# espyollucopy.net
KiCad netlist of a schematic drawn in EAGLE
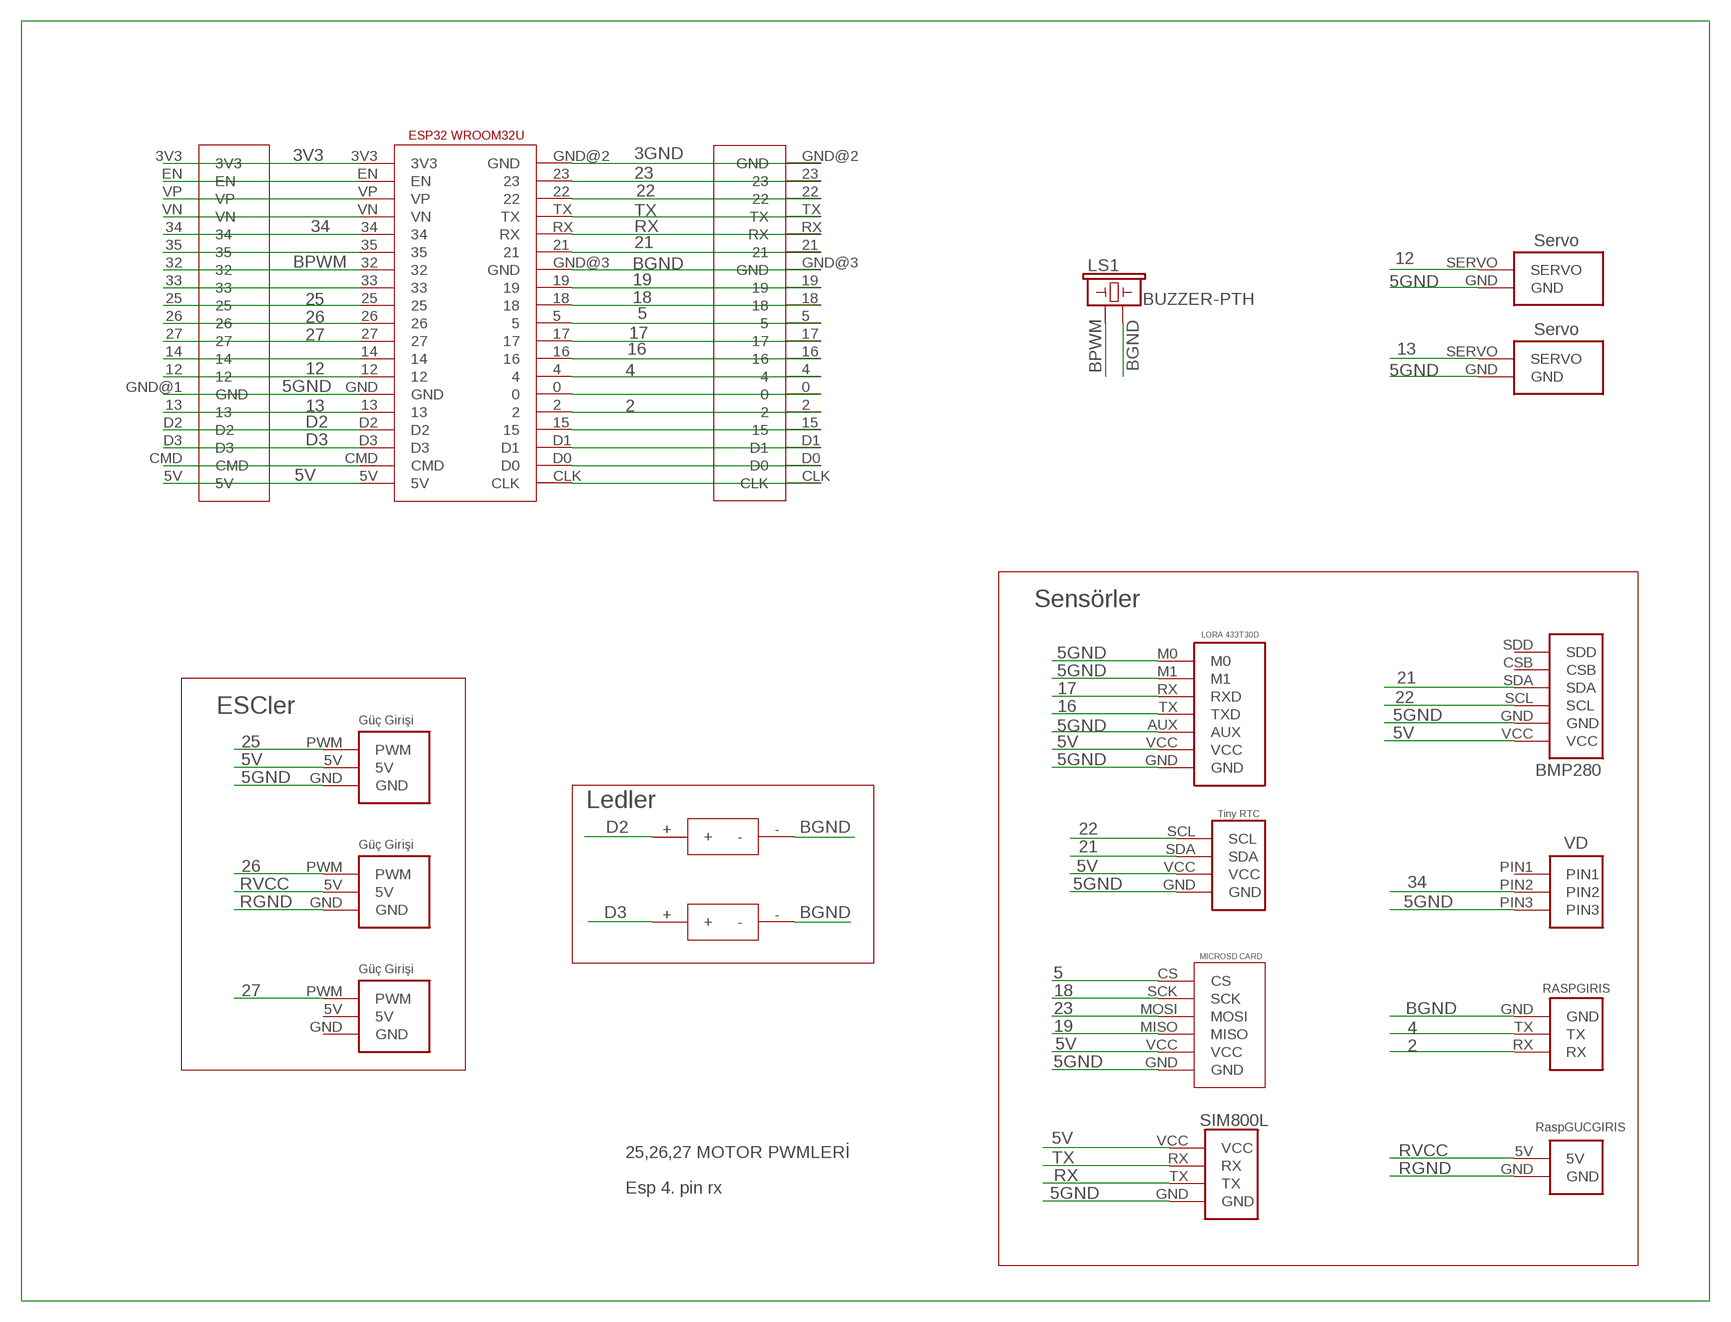
[diagram p0: schematic, sheet 1]

(export (version "E")
  (design (tool "Eeschema 10.0.6"))
  (components
    (comp (ref "BMP1")
      (value "BMP280")
      (footprint "eagle-import:BMP280")
      (libsource (lib "eagle-import") (part "BMP280"))
    )
    (comp (ref "LS1")
      (value "BUZZER-PTH")
      (footprint "eagle-import:BUZZER-12MM")
      (libsource (lib "eagle-import") (part "BUZZER-PTH"))
    )
    (comp (ref "U$1")
      (value "TINYRTC")
      (footprint "eagle-import:TINYRTC")
      (libsource (lib "eagle-import") (part "TINYRTC"))
    )
    (comp (ref "U$2")
      (value "VOLTAGE_DIVIDER")
      (footprint "eagle-import:VOLTAGE_DIVIDER")
      (libsource (lib "eagle-import") (part "VOLTAGE_DIVIDER"))
    )
    (comp (ref "U$3")
      (value "RASPGIRIS")
      (footprint "eagle-import:RASPGIRIS")
      (libsource (lib "eagle-import") (part "RASPGIRIS"))
    )
    (comp (ref "U$4")
      (value "ESP32WROOM32U")
      (footprint "eagle-import:ESP32WROOM32U")
      (libsource (lib "eagle-import") (part "ESP32WROOM32U"))
    )
    (comp (ref "U$5")
      (value "LORAFULLSIZE")
      (footprint "eagle-import:LORAFULLSIZE")
      (libsource (lib "eagle-import") (part "LORAFULLSIZE"))
    )
    (comp (ref "U$6")
      (value "MICROSD_CARD")
      (footprint "eagle-import:MICROSD_CARD")
      (libsource (lib "eagle-import") (part "MICROSD_CARD"))
    )
    (comp (ref "U$7")
      (value "SERVO_SIGNAL")
      (footprint "eagle-import:SERVO_SIGNAL")
      (libsource (lib "eagle-import") (part "SERVO_SIGNAL"))
    )
    (comp (ref "U$8")
      (value "SIM800L")
      (footprint "eagle-import:SIM800L")
      (libsource (lib "eagle-import") (part "SIM800L"))
    )
    (comp (ref "U$9")
      (value "SERVO_SIGNAL")
      (footprint "eagle-import:SERVO_SIGNAL")
      (libsource (lib "eagle-import") (part "SERVO_SIGNAL"))
    )
    (comp (ref "U$10")
      (value "RASPGUCGIRIS")
      (footprint "eagle-import:RASPGUCGIRIS")
      (libsource (lib "eagle-import") (part "RASPGUCGIRIS"))
    )
    (comp (ref "U$11")
      (value "ESC_GIRIS")
      (footprint "eagle-import:ESC_GIRIS")
      (libsource (lib "eagle-import") (part "ESC_GIRIS"))
    )
    (comp (ref "U$12")
      (value "ESC_GIRIS")
      (footprint "eagle-import:ESC_GIRIS")
      (libsource (lib "eagle-import") (part "ESC_GIRIS"))
    )
    (comp (ref "U$13")
      (value "ESC_GIRIS")
      (footprint "eagle-import:ESC_GIRIS")
      (libsource (lib "eagle-import") (part "ESC_GIRIS"))
    )
    (comp (ref "U$14")
      (value "ESPSAGPIN")
      (footprint "eagle-import:ESPSAGPIN")
      (libsource (lib "eagle-import") (part "ESPSAGPIN"))
    )
    (comp (ref "U$15")
      (value "ESPSOLPIN")
      (footprint "eagle-import:ESPSOLPIN")
      (libsource (lib "eagle-import") (part "ESPSOLPIN"))
    )
    (comp (ref "U$17")
      (value "LED")
      (footprint "eagle-import:LED")
      (libsource (lib "eagle-import") (part "LED"))
    )
    (comp (ref "U$18")
      (value "LED")
      (footprint "eagle-import:LED")
      (libsource (lib "eagle-import") (part "LED"))
    )
  )
  (nets
    (net (code "1") (name "/2") (class "Default")
      (node (ref "U$14") (pin "2") (pinfunction "2_2") (pintype "bidirectional"))
      (node (ref "U$3") (pin "RX") (pinfunction "RX_RX") (pintype "bidirectional"))
      (node (ref "U$4") (pin "2") (pinfunction "2_2") (pintype "bidirectional"))
    )
    (net (code "2") (name "/3GND") (class "Default")
      (node (ref "U$14") (pin "GND@2") (pinfunction "GND_GND@2") (pintype "bidirectional"))
      (node (ref "U$4") (pin "GND@2") (pinfunction "GND_GND@2") (pintype "bidirectional"))
    )
    (net (code "3") (name "/3V3") (class "Default")
      (node (ref "U$15") (pin "3V3") (pinfunction "3V3_3V3") (pintype "bidirectional"))
      (node (ref "U$4") (pin "3V3") (pinfunction "3V3_3V3") (pintype "bidirectional"))
    )
    (net (code "4") (name "/4") (class "Default")
      (node (ref "U$14") (pin "4") (pinfunction "4_4") (pintype "bidirectional"))
      (node (ref "U$3") (pin "TX") (pinfunction "TX_TX") (pintype "bidirectional"))
      (node (ref "U$4") (pin "4") (pinfunction "4_4") (pintype "bidirectional"))
    )
    (net (code "5") (name "/5") (class "Default")
      (node (ref "U$14") (pin "5") (pinfunction "5_5") (pintype "bidirectional"))
      (node (ref "U$4") (pin "5") (pinfunction "5_5") (pintype "bidirectional"))
      (node (ref "U$6") (pin "CS") (pinfunction "CS_CS") (pintype "bidirectional"))
    )
    (net (code "6") (name "/5GND") (class "Default")
      (node (ref "BMP1") (pin "GND") (pinfunction "GND_GND") (pintype "bidirectional"))
      (node (ref "U$1") (pin "GND") (pinfunction "GND_GND") (pintype "bidirectional"))
      (node (ref "U$11") (pin "GND") (pinfunction "GND_GND") (pintype "bidirectional"))
      (node (ref "U$15") (pin "GND@1") (pinfunction "GND_GND@1") (pintype "bidirectional"))
      (node (ref "U$2") (pin "PIN3") (pinfunction "PIN3_PIN3") (pintype "bidirectional"))
      (node (ref "U$4") (pin "GND") (pinfunction "GND_GND") (pintype "bidirectional"))
      (node (ref "U$5") (pin "AUX") (pinfunction "AUX_AUX") (pintype "bidirectional"))
      (node (ref "U$5") (pin "GND") (pinfunction "GND_GND") (pintype "bidirectional"))
      (node (ref "U$5") (pin "M0") (pinfunction "M0_M0") (pintype "bidirectional"))
      (node (ref "U$5") (pin "M1") (pinfunction "M1_M1") (pintype "bidirectional"))
      (node (ref "U$6") (pin "GND") (pinfunction "GND_GND") (pintype "bidirectional"))
      (node (ref "U$7") (pin "GND") (pinfunction "GND_GND") (pintype "bidirectional"))
      (node (ref "U$8") (pin "GND") (pinfunction "GND_GND") (pintype "bidirectional"))
      (node (ref "U$9") (pin "GND") (pinfunction "GND_GND") (pintype "bidirectional"))
    )
    (net (code "7") (name "/5V") (class "Default")
      (node (ref "BMP1") (pin "VCC") (pinfunction "VCC_VCC") (pintype "bidirectional"))
      (node (ref "U$1") (pin "VCC") (pinfunction "VCC_VCC") (pintype "bidirectional"))
      (node (ref "U$11") (pin "5V") (pinfunction "5V_5V") (pintype "bidirectional"))
      (node (ref "U$15") (pin "5V") (pinfunction "5V_5V") (pintype "bidirectional"))
      (node (ref "U$4") (pin "5V") (pinfunction "5V_5V") (pintype "bidirectional"))
      (node (ref "U$5") (pin "VCC") (pinfunction "VCC_VCC") (pintype "bidirectional"))
      (node (ref "U$6") (pin "VCC") (pinfunction "VCC_VCC") (pintype "bidirectional"))
      (node (ref "U$8") (pin "VCC") (pinfunction "VCC_VCC") (pintype "bidirectional"))
    )
    (net (code "8") (name "/12") (class "Default")
      (node (ref "U$15") (pin "12") (pinfunction "12_12") (pintype "bidirectional"))
      (node (ref "U$4") (pin "12") (pinfunction "12_12") (pintype "bidirectional"))
      (node (ref "U$7") (pin "SERVO") (pinfunction "SERVO_SERVO") (pintype "bidirectional"))
    )
    (net (code "9") (name "/13") (class "Default")
      (node (ref "U$15") (pin "13") (pinfunction "13_13") (pintype "bidirectional"))
      (node (ref "U$4") (pin "13") (pinfunction "13_13") (pintype "bidirectional"))
      (node (ref "U$9") (pin "SERVO") (pinfunction "SERVO_SERVO") (pintype "bidirectional"))
    )
    (net (code "10") (name "/16") (class "Default")
      (node (ref "U$14") (pin "16") (pinfunction "16_16") (pintype "bidirectional"))
      (node (ref "U$4") (pin "16") (pinfunction "16_16") (pintype "bidirectional"))
      (node (ref "U$5") (pin "TX") (pinfunction "TXD_TX") (pintype "bidirectional"))
    )
    (net (code "11") (name "/17") (class "Default")
      (node (ref "U$14") (pin "17") (pinfunction "17_17") (pintype "bidirectional"))
      (node (ref "U$4") (pin "17") (pinfunction "17_17") (pintype "bidirectional"))
      (node (ref "U$5") (pin "RX") (pinfunction "RXD_RX") (pintype "bidirectional"))
    )
    (net (code "12") (name "/18") (class "Default")
      (node (ref "U$14") (pin "18") (pinfunction "18_18") (pintype "bidirectional"))
      (node (ref "U$4") (pin "18") (pinfunction "18_18") (pintype "bidirectional"))
      (node (ref "U$6") (pin "SCK") (pinfunction "SCK_SCK") (pintype "bidirectional"))
    )
    (net (code "13") (name "/19") (class "Default")
      (node (ref "U$14") (pin "19") (pinfunction "19_19") (pintype "bidirectional"))
      (node (ref "U$4") (pin "19") (pinfunction "19_19") (pintype "bidirectional"))
      (node (ref "U$6") (pin "MISO") (pinfunction "MISO_MISO") (pintype "bidirectional"))
    )
    (net (code "14") (name "/21") (class "Default")
      (node (ref "BMP1") (pin "SDA") (pinfunction "SDA_SDA") (pintype "bidirectional"))
      (node (ref "U$1") (pin "SDA") (pinfunction "SDA_SDA") (pintype "bidirectional"))
      (node (ref "U$14") (pin "21") (pinfunction "21_21") (pintype "bidirectional"))
      (node (ref "U$4") (pin "21") (pinfunction "21_21") (pintype "bidirectional"))
    )
    (net (code "15") (name "/22") (class "Default")
      (node (ref "BMP1") (pin "SCL") (pinfunction "SCL_SCL") (pintype "bidirectional"))
      (node (ref "U$1") (pin "SCL") (pinfunction "SCL_SCL") (pintype "bidirectional"))
      (node (ref "U$14") (pin "22") (pinfunction "22_22") (pintype "bidirectional"))
      (node (ref "U$4") (pin "22") (pinfunction "22_22") (pintype "bidirectional"))
    )
    (net (code "16") (name "/23") (class "Default")
      (node (ref "U$14") (pin "23") (pinfunction "23_23") (pintype "bidirectional"))
      (node (ref "U$4") (pin "23") (pinfunction "23_23") (pintype "bidirectional"))
      (node (ref "U$6") (pin "MOSI") (pinfunction "MOSI_MOSI") (pintype "bidirectional"))
    )
    (net (code "17") (name "/25") (class "Default")
      (node (ref "U$11") (pin "PWM") (pinfunction "PWM_PWM") (pintype "bidirectional"))
      (node (ref "U$15") (pin "25") (pinfunction "25_25") (pintype "bidirectional"))
      (node (ref "U$4") (pin "25") (pinfunction "25_25") (pintype "bidirectional"))
    )
    (net (code "18") (name "/26") (class "Default")
      (node (ref "U$12") (pin "PWM") (pinfunction "PWM_PWM") (pintype "bidirectional"))
      (node (ref "U$15") (pin "26") (pinfunction "26_26") (pintype "bidirectional"))
      (node (ref "U$4") (pin "26") (pinfunction "26_26") (pintype "bidirectional"))
    )
    (net (code "19") (name "/27") (class "Default")
      (node (ref "U$13") (pin "PWM") (pinfunction "PWM_PWM") (pintype "bidirectional"))
      (node (ref "U$15") (pin "27") (pinfunction "27_27") (pintype "bidirectional"))
      (node (ref "U$4") (pin "27") (pinfunction "27_27") (pintype "bidirectional"))
    )
    (net (code "20") (name "/34") (class "Default")
      (node (ref "U$15") (pin "34") (pinfunction "34_34") (pintype "bidirectional"))
      (node (ref "U$2") (pin "PIN2") (pinfunction "PIN2_PIN2") (pintype "bidirectional"))
      (node (ref "U$4") (pin "34") (pinfunction "34_34") (pintype "bidirectional"))
    )
    (net (code "21") (name "/BGND") (class "Default")
      (node (ref "LS1") (pin "-") (pinfunction "2_-") (pintype "passive"))
      (node (ref "U$14") (pin "GND@3") (pinfunction "GND_GND@3") (pintype "bidirectional"))
      (node (ref "U$17") (pin "-") (pinfunction "-_-") (pintype "bidirectional"))
      (node (ref "U$18") (pin "-") (pinfunction "-_-") (pintype "bidirectional"))
      (node (ref "U$3") (pin "GND") (pinfunction "GND_GND") (pintype "bidirectional"))
      (node (ref "U$4") (pin "GND@3") (pinfunction "GND_GND@3") (pintype "bidirectional"))
    )
    (net (code "22") (name "/BPWM") (class "Default")
      (node (ref "LS1") (pin "+") (pinfunction "1_+") (pintype "passive"))
      (node (ref "U$15") (pin "32") (pinfunction "32_32") (pintype "bidirectional"))
      (node (ref "U$4") (pin "32") (pinfunction "32_32") (pintype "bidirectional"))
    )
    (net (code "23") (name "/D2") (class "Default")
      (node (ref "U$15") (pin "D2") (pinfunction "D2_D2") (pintype "bidirectional"))
      (node (ref "U$17") (pin "+") (pinfunction "+_+") (pintype "bidirectional"))
      (node (ref "U$4") (pin "D2") (pinfunction "D2_D2") (pintype "bidirectional"))
    )
    (net (code "24") (name "/D3") (class "Default")
      (node (ref "U$15") (pin "D3") (pinfunction "D3_D3") (pintype "bidirectional"))
      (node (ref "U$18") (pin "+") (pinfunction "+_+") (pintype "bidirectional"))
      (node (ref "U$4") (pin "D3") (pinfunction "D3_D3") (pintype "bidirectional"))
    )
    (net (code "25") (name "/RGND") (class "Default")
      (node (ref "U$10") (pin "GND") (pinfunction "GND_GND") (pintype "bidirectional"))
      (node (ref "U$12") (pin "GND") (pinfunction "GND_GND") (pintype "bidirectional"))
    )
    (net (code "26") (name "/RVCC") (class "Default")
      (node (ref "U$10") (pin "5V") (pinfunction "5V_5V") (pintype "bidirectional"))
      (node (ref "U$12") (pin "5V") (pinfunction "5V_5V") (pintype "bidirectional"))
    )
    (net (code "27") (name "/RX") (class "Default")
      (node (ref "U$14") (pin "RX") (pinfunction "RX_RX") (pintype "bidirectional"))
      (node (ref "U$4") (pin "RX") (pinfunction "RX_RX") (pintype "bidirectional"))
      (node (ref "U$8") (pin "TX") (pinfunction "TX_TX") (pintype "bidirectional"))
    )
    (net (code "28") (name "/TX") (class "Default")
      (node (ref "U$14") (pin "TX") (pinfunction "TX_TX") (pintype "bidirectional"))
      (node (ref "U$4") (pin "TX") (pinfunction "TX_TX") (pintype "bidirectional"))
      (node (ref "U$8") (pin "RX") (pinfunction "RX_RX") (pintype "bidirectional"))
    )
    (net (code "29") (name "Net-(U$14-Pad0)") (class "Default")
      (node (ref "U$14") (pin "0") (pinfunction "0_0") (pintype "bidirectional"))
      (node (ref "U$4") (pin "0") (pinfunction "0_0") (pintype "bidirectional"))
    )
    (net (code "30") (name "Net-(U$14-Pad15)") (class "Default")
      (node (ref "U$14") (pin "15") (pinfunction "15_15") (pintype "bidirectional"))
      (node (ref "U$4") (pin "15") (pinfunction "15_15") (pintype "bidirectional"))
    )
    (net (code "31") (name "Net-(U$14-PadCLK)") (class "Default")
      (node (ref "U$14") (pin "CLK") (pinfunction "CLK_CLK") (pintype "bidirectional"))
      (node (ref "U$4") (pin "CLK") (pinfunction "CLK_CLK") (pintype "bidirectional"))
    )
    (net (code "32") (name "Net-(U$14-PadD0)") (class "Default")
      (node (ref "U$14") (pin "D0") (pinfunction "D0_D0") (pintype "bidirectional"))
      (node (ref "U$4") (pin "D0") (pinfunction "D0_D0") (pintype "bidirectional"))
    )
    (net (code "33") (name "Net-(U$14-PadD1)") (class "Default")
      (node (ref "U$14") (pin "D1") (pinfunction "D1_D1") (pintype "bidirectional"))
      (node (ref "U$4") (pin "D1") (pinfunction "D1_D1") (pintype "bidirectional"))
    )
    (net (code "34") (name "Net-(U$15-Pad14)") (class "Default")
      (node (ref "U$15") (pin "14") (pinfunction "14_14") (pintype "bidirectional"))
      (node (ref "U$4") (pin "14") (pinfunction "14_14") (pintype "bidirectional"))
    )
    (net (code "35") (name "Net-(U$15-Pad33)") (class "Default")
      (node (ref "U$15") (pin "33") (pinfunction "33_33") (pintype "bidirectional"))
      (node (ref "U$4") (pin "33") (pinfunction "33_33") (pintype "bidirectional"))
    )
    (net (code "36") (name "Net-(U$15-Pad35)") (class "Default")
      (node (ref "U$15") (pin "35") (pinfunction "35_35") (pintype "bidirectional"))
      (node (ref "U$4") (pin "35") (pinfunction "35_35") (pintype "bidirectional"))
    )
    (net (code "37") (name "Net-(U$15-PadCMD)") (class "Default")
      (node (ref "U$15") (pin "CMD") (pinfunction "CMD_CMD") (pintype "bidirectional"))
      (node (ref "U$4") (pin "CMD") (pinfunction "CMD_CMD") (pintype "bidirectional"))
    )
    (net (code "38") (name "Net-(U$15-PadEN)") (class "Default")
      (node (ref "U$15") (pin "EN") (pinfunction "EN_EN") (pintype "bidirectional"))
      (node (ref "U$4") (pin "EN") (pinfunction "EN_EN") (pintype "bidirectional"))
    )
    (net (code "39") (name "Net-(U$15-PadVN)") (class "Default")
      (node (ref "U$15") (pin "VN") (pinfunction "VN_VN") (pintype "bidirectional"))
      (node (ref "U$4") (pin "VN") (pinfunction "VN_VN") (pintype "bidirectional"))
    )
    (net (code "40") (name "Net-(U$15-PadVP)") (class "Default")
      (node (ref "U$15") (pin "VP") (pinfunction "VP_VP") (pintype "bidirectional"))
      (node (ref "U$4") (pin "VP") (pinfunction "VP_VP") (pintype "bidirectional"))
    )
    (net (code "41") (name "unconnected-(BMP1-PadCSB)") (class "Default")
      (node (ref "BMP1") (pin "CSB") (pinfunction "CSB_CSB") (pintype "bidirectional"))
    )
    (net (code "42") (name "unconnected-(BMP1-PadSDD)") (class "Default")
      (node (ref "BMP1") (pin "SDD") (pinfunction "SDD_SDD") (pintype "bidirectional"))
    )
    (net (code "43") (name "unconnected-(U$2-PadPIN1)") (class "Default")
      (node (ref "U$2") (pin "PIN1") (pinfunction "PIN1_PIN1") (pintype "bidirectional"))
    )
    (net (code "44") (name "unconnected-(U$13-Pad5V)") (class "Default")
      (node (ref "U$13") (pin "5V") (pinfunction "5V_5V") (pintype "bidirectional"))
    )
    (net (code "45") (name "unconnected-(U$13-PadGND)") (class "Default")
      (node (ref "U$13") (pin "GND") (pinfunction "GND_GND") (pintype "bidirectional"))
    )
  )
)
